# VSSOP-8.net
KiCad netlist of a schematic drawn in EAGLE
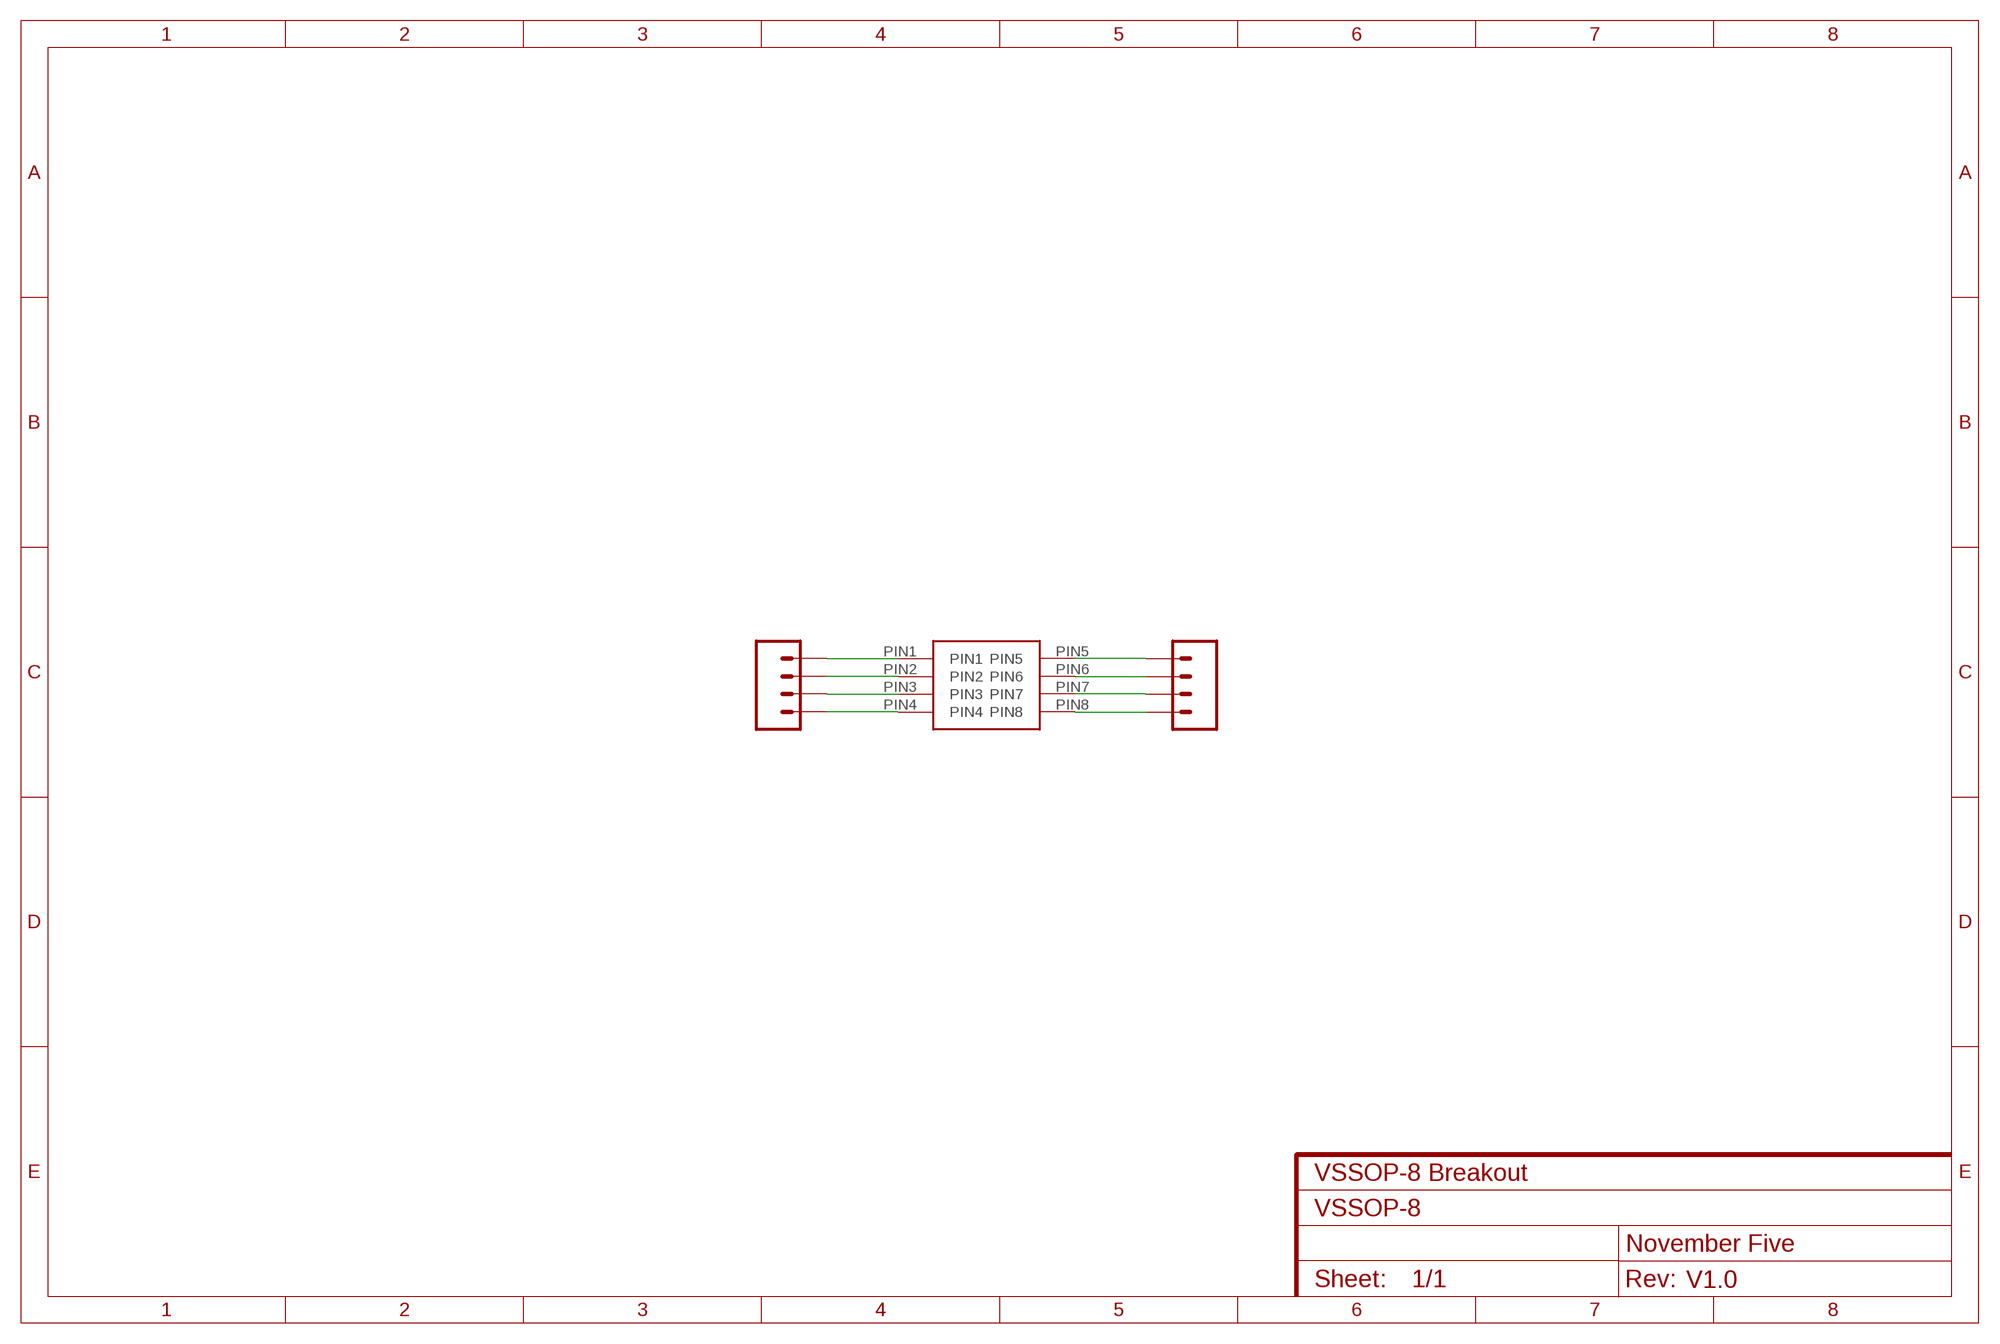
[diagram p0: schematic, sheet 1]

(export (version "E")
  (design (tool "Eeschema 10.0.6"))
  (components
    (comp (ref "J1")
      (value "CONN_04")
      (footprint "eagle-import:1X04")
      (libsource (lib "eagle-import") (part "CONN_04"))
    )
    (comp (ref "J2")
      (value "CONN_04")
      (footprint "eagle-import:1X04")
      (libsource (lib "eagle-import") (part "CONN_04"))
    )
    (comp (ref "U$1")
      (value "VSSOP-8")
      (footprint "eagle-import:VSSOP-8")
      (libsource (lib "eagle-import") (part "VSSOP-8"))
    )
  )
  (nets
    (net (code "1") (name "Net-(J1-Pad1)") (class "Default")
      (node (ref "J1") (pin "1") (pinfunction "1_1") (pintype "passive"))
      (node (ref "U$1") (pin "PIN4") (pinfunction "PIN4_PIN4") (pintype "open_collector"))
    )
    (net (code "2") (name "Net-(J1-Pad2)") (class "Default")
      (node (ref "J1") (pin "2") (pinfunction "2_2") (pintype "passive"))
      (node (ref "U$1") (pin "PIN3") (pinfunction "PIN3_PIN3") (pintype "open_collector"))
    )
    (net (code "3") (name "Net-(J1-Pad3)") (class "Default")
      (node (ref "J1") (pin "3") (pinfunction "3_3") (pintype "passive"))
      (node (ref "U$1") (pin "PIN2") (pinfunction "PIN2_PIN2") (pintype "open_collector"))
    )
    (net (code "4") (name "Net-(J1-Pad4)") (class "Default")
      (node (ref "J1") (pin "4") (pinfunction "4_4") (pintype "passive"))
      (node (ref "U$1") (pin "PIN1") (pinfunction "PIN1_PIN1") (pintype "open_collector"))
    )
    (net (code "5") (name "Net-(J2-Pad1)") (class "Default")
      (node (ref "J2") (pin "1") (pinfunction "1_1") (pintype "passive"))
      (node (ref "U$1") (pin "PIN5") (pinfunction "PIN5_PIN5") (pintype "open_collector"))
    )
    (net (code "6") (name "Net-(J2-Pad2)") (class "Default")
      (node (ref "J2") (pin "2") (pinfunction "2_2") (pintype "passive"))
      (node (ref "U$1") (pin "PIN6") (pinfunction "PIN6_PIN6") (pintype "open_collector"))
    )
    (net (code "7") (name "Net-(J2-Pad3)") (class "Default")
      (node (ref "J2") (pin "3") (pinfunction "3_3") (pintype "passive"))
      (node (ref "U$1") (pin "PIN7") (pinfunction "PIN7_PIN7") (pintype "open_collector"))
    )
    (net (code "8") (name "Net-(J2-Pad4)") (class "Default")
      (node (ref "J2") (pin "4") (pinfunction "4_4") (pintype "passive"))
      (node (ref "U$1") (pin "PIN8") (pinfunction "PIN8_PIN8") (pintype "open_collector"))
    )
  )
)
